# sHallAdapter.net
KiCad netlist of a schematic drawn in EAGLE
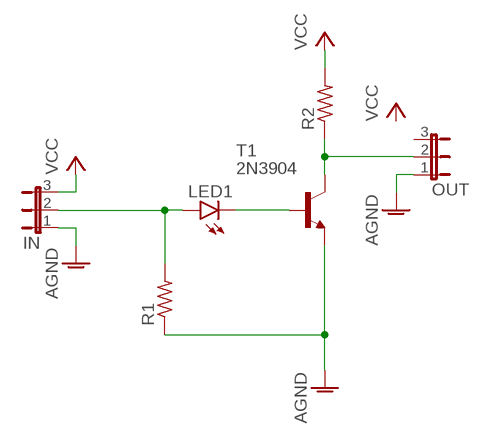
[diagram p0: schematic, sheet 1]

(export (version "E")
  (design (tool "Eeschema 10.0.6"))
  (components
    (comp (ref "IN")
      (value "JP2E")
      (footprint "eagle-import:JP2")
      (libsource (lib "eagle-import") (part "JP2E"))
    )
    (comp (ref "LED1")
      (value "LED3MM")
      (footprint "eagle-import:LED3MM")
      (libsource (lib "eagle-import") (part "LED3MM"))
    )
    (comp (ref "OUT")
      (value "JP2E")
      (footprint "eagle-import:JP2")
      (libsource (lib "eagle-import") (part "JP2E"))
    )
    (comp (ref "R1")
      (value "R-US_R0805W")
      (footprint "eagle-import:R0805W")
      (libsource (lib "eagle-import") (part "R-US_R0805W"))
    )
    (comp (ref "R2")
      (value "R-US_R0805W")
      (footprint "eagle-import:R0805W")
      (libsource (lib "eagle-import") (part "R-US_R0805W"))
    )
    (comp (ref "T1")
      (value "2N3904")
      (footprint "eagle-import:TO92")
      (libsource (lib "eagle-import") (part "2N3904"))
    )
  )
  (nets
    (net (code "1") (name "AGND") (class "Default")
      (node (ref "IN") (pin "1") (pinfunction "1_1") (pintype "passive"))
      (node (ref "OUT") (pin "1") (pinfunction "1_1") (pintype "passive"))
      (node (ref "R1") (pin "1") (pinfunction "1_1") (pintype "passive"))
      (node (ref "T1") (pin "3") (pinfunction "E_3") (pintype "passive"))
    )
    (net (code "2") (name "Net-(IN-Pad2)") (class "Default")
      (node (ref "IN") (pin "2") (pinfunction "2_2") (pintype "passive"))
      (node (ref "LED1") (pin "A") (pinfunction "A_A") (pintype "passive"))
      (node (ref "R1") (pin "2") (pinfunction "2_2") (pintype "passive"))
    )
    (net (code "3") (name "Net-(LED1-C)") (class "Default")
      (node (ref "LED1") (pin "K") (pinfunction "C_K") (pintype "passive"))
      (node (ref "T1") (pin "2") (pinfunction "B_2") (pintype "passive"))
    )
    (net (code "4") (name "Net-(T1-C)") (class "Default")
      (node (ref "OUT") (pin "2") (pinfunction "2_2") (pintype "passive"))
      (node (ref "R2") (pin "1") (pinfunction "1_1") (pintype "passive"))
      (node (ref "T1") (pin "1") (pinfunction "C_1") (pintype "passive"))
    )
    (net (code "5") (name "VCC") (class "Default")
      (node (ref "IN") (pin "3") (pinfunction "3_3") (pintype "passive"))
      (node (ref "R2") (pin "2") (pinfunction "2_2") (pintype "passive"))
    )
    (net (code "6") (name "unconnected-(OUT-Pad3)") (class "Default")
      (node (ref "OUT") (pin "3") (pinfunction "3_3") (pintype "passive"))
    )
  )
)
